# LED_0.net
KiCad netlist of a schematic drawn in Altium Designer
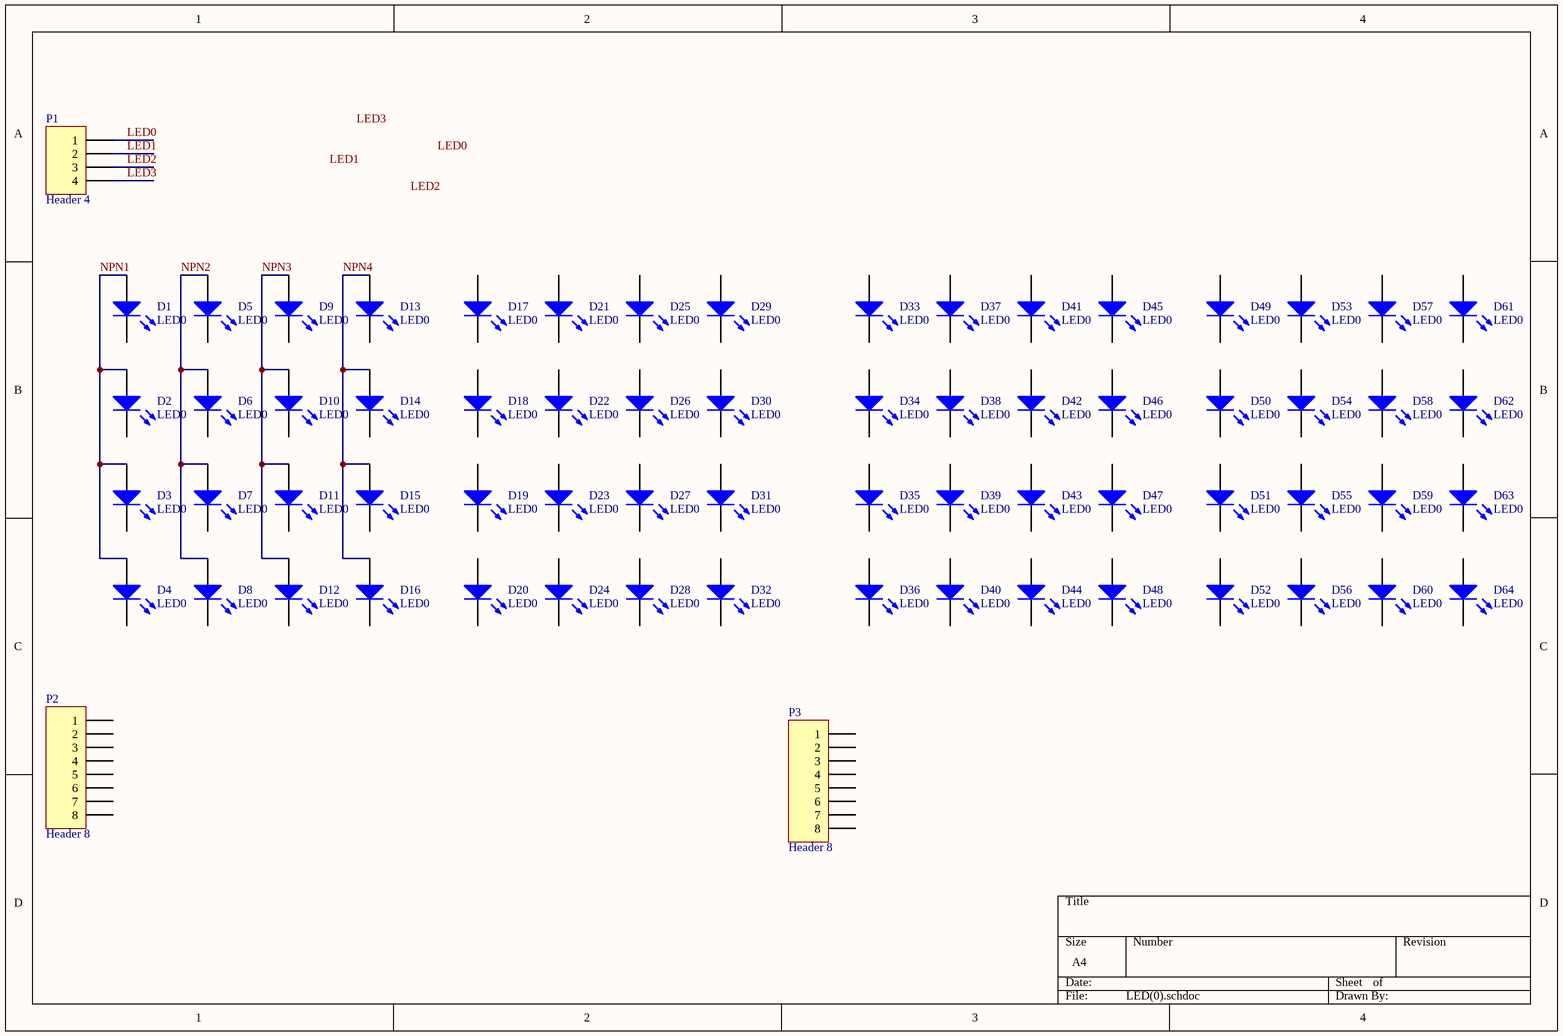
[diagram p0: LED(0).schdoc]

(export (version "E")
  (design (tool "Eeschema 10.0.6"))
  (components
    (comp (ref "D1")
      (value "LED0")
      (footprint "LED-0")
      (description "Typical INFRARED GaAs LED")
      (fields (field (name "PUBLISHER") "Altium Limited"))
      (libsource (lib "Miscellaneous Devices") (part "LED0"))
    )
    (comp (ref "D2")
      (value "LED0")
      (footprint "LED-0")
      (description "Typical INFRARED GaAs LED")
      (fields (field (name "PUBLISHER") "Altium Limited"))
      (libsource (lib "Miscellaneous Devices") (part "LED0"))
    )
    (comp (ref "D3")
      (value "LED0")
      (footprint "LED-0")
      (description "Typical INFRARED GaAs LED")
      (fields (field (name "PUBLISHER") "Altium Limited"))
      (libsource (lib "Miscellaneous Devices") (part "LED0"))
    )
    (comp (ref "D4")
      (value "LED0")
      (footprint "LED-0")
      (description "Typical INFRARED GaAs LED")
      (fields (field (name "PUBLISHER") "Altium Limited"))
      (libsource (lib "Miscellaneous Devices") (part "LED0"))
    )
    (comp (ref "D5")
      (value "LED0")
      (footprint "LED-0")
      (description "Typical INFRARED GaAs LED")
      (fields (field (name "PUBLISHER") "Altium Limited"))
      (libsource (lib "Miscellaneous Devices") (part "LED0"))
    )
    (comp (ref "D6")
      (value "LED0")
      (footprint "LED-0")
      (description "Typical INFRARED GaAs LED")
      (fields (field (name "PUBLISHER") "Altium Limited"))
      (libsource (lib "Miscellaneous Devices") (part "LED0"))
    )
    (comp (ref "D7")
      (value "LED0")
      (footprint "LED-0")
      (description "Typical INFRARED GaAs LED")
      (fields (field (name "PUBLISHER") "Altium Limited"))
      (libsource (lib "Miscellaneous Devices") (part "LED0"))
    )
    (comp (ref "D8")
      (value "LED0")
      (footprint "LED-0")
      (description "Typical INFRARED GaAs LED")
      (fields (field (name "PUBLISHER") "Altium Limited"))
      (libsource (lib "Miscellaneous Devices") (part "LED0"))
    )
    (comp (ref "D9")
      (value "LED0")
      (footprint "LED-0")
      (description "Typical INFRARED GaAs LED")
      (fields (field (name "PUBLISHER") "Altium Limited"))
      (libsource (lib "Miscellaneous Devices") (part "LED0"))
    )
    (comp (ref "D10")
      (value "LED0")
      (footprint "LED-0")
      (description "Typical INFRARED GaAs LED")
      (fields (field (name "PUBLISHER") "Altium Limited"))
      (libsource (lib "Miscellaneous Devices") (part "LED0"))
    )
    (comp (ref "D11")
      (value "LED0")
      (footprint "LED-0")
      (description "Typical INFRARED GaAs LED")
      (fields (field (name "PUBLISHER") "Altium Limited"))
      (libsource (lib "Miscellaneous Devices") (part "LED0"))
    )
    (comp (ref "D12")
      (value "LED0")
      (footprint "LED-0")
      (description "Typical INFRARED GaAs LED")
      (fields (field (name "PUBLISHER") "Altium Limited"))
      (libsource (lib "Miscellaneous Devices") (part "LED0"))
    )
    (comp (ref "D13")
      (value "LED0")
      (footprint "LED-0")
      (description "Typical INFRARED GaAs LED")
      (fields (field (name "PUBLISHER") "Altium Limited"))
      (libsource (lib "Miscellaneous Devices") (part "LED0"))
    )
    (comp (ref "D14")
      (value "LED0")
      (footprint "LED-0")
      (description "Typical INFRARED GaAs LED")
      (fields (field (name "PUBLISHER") "Altium Limited"))
      (libsource (lib "Miscellaneous Devices") (part "LED0"))
    )
    (comp (ref "D15")
      (value "LED0")
      (footprint "LED-0")
      (description "Typical INFRARED GaAs LED")
      (fields (field (name "PUBLISHER") "Altium Limited"))
      (libsource (lib "Miscellaneous Devices") (part "LED0"))
    )
    (comp (ref "D16")
      (value "LED0")
      (footprint "LED-0")
      (description "Typical INFRARED GaAs LED")
      (fields (field (name "PUBLISHER") "Altium Limited"))
      (libsource (lib "Miscellaneous Devices") (part "LED0"))
    )
    (comp (ref "D17")
      (value "LED0")
      (footprint "LED-0")
      (description "Typical INFRARED GaAs LED")
      (fields (field (name "PUBLISHER") "Altium Limited"))
      (libsource (lib "Miscellaneous Devices") (part "LED0"))
    )
    (comp (ref "D18")
      (value "LED0")
      (footprint "LED-0")
      (description "Typical INFRARED GaAs LED")
      (fields (field (name "PUBLISHER") "Altium Limited"))
      (libsource (lib "Miscellaneous Devices") (part "LED0"))
    )
    (comp (ref "D19")
      (value "LED0")
      (footprint "LED-0")
      (description "Typical INFRARED GaAs LED")
      (fields (field (name "PUBLISHER") "Altium Limited"))
      (libsource (lib "Miscellaneous Devices") (part "LED0"))
    )
    (comp (ref "D20")
      (value "LED0")
      (footprint "LED-0")
      (description "Typical INFRARED GaAs LED")
      (fields (field (name "PUBLISHER") "Altium Limited"))
      (libsource (lib "Miscellaneous Devices") (part "LED0"))
    )
    (comp (ref "D21")
      (value "LED0")
      (footprint "LED-0")
      (description "Typical INFRARED GaAs LED")
      (fields (field (name "PUBLISHER") "Altium Limited"))
      (libsource (lib "Miscellaneous Devices") (part "LED0"))
    )
    (comp (ref "D22")
      (value "LED0")
      (footprint "LED-0")
      (description "Typical INFRARED GaAs LED")
      (fields (field (name "PUBLISHER") "Altium Limited"))
      (libsource (lib "Miscellaneous Devices") (part "LED0"))
    )
    (comp (ref "D23")
      (value "LED0")
      (footprint "LED-0")
      (description "Typical INFRARED GaAs LED")
      (fields (field (name "PUBLISHER") "Altium Limited"))
      (libsource (lib "Miscellaneous Devices") (part "LED0"))
    )
    (comp (ref "D24")
      (value "LED0")
      (footprint "LED-0")
      (description "Typical INFRARED GaAs LED")
      (fields (field (name "PUBLISHER") "Altium Limited"))
      (libsource (lib "Miscellaneous Devices") (part "LED0"))
    )
    (comp (ref "D25")
      (value "LED0")
      (footprint "LED-0")
      (description "Typical INFRARED GaAs LED")
      (fields (field (name "PUBLISHER") "Altium Limited"))
      (libsource (lib "Miscellaneous Devices") (part "LED0"))
    )
    (comp (ref "D26")
      (value "LED0")
      (footprint "LED-0")
      (description "Typical INFRARED GaAs LED")
      (fields (field (name "PUBLISHER") "Altium Limited"))
      (libsource (lib "Miscellaneous Devices") (part "LED0"))
    )
    (comp (ref "D27")
      (value "LED0")
      (footprint "LED-0")
      (description "Typical INFRARED GaAs LED")
      (fields (field (name "PUBLISHER") "Altium Limited"))
      (libsource (lib "Miscellaneous Devices") (part "LED0"))
    )
    (comp (ref "D28")
      (value "LED0")
      (footprint "LED-0")
      (description "Typical INFRARED GaAs LED")
      (fields (field (name "PUBLISHER") "Altium Limited"))
      (libsource (lib "Miscellaneous Devices") (part "LED0"))
    )
    (comp (ref "D29")
      (value "LED0")
      (footprint "LED-0")
      (description "Typical INFRARED GaAs LED")
      (fields (field (name "PUBLISHER") "Altium Limited"))
      (libsource (lib "Miscellaneous Devices") (part "LED0"))
    )
    (comp (ref "D30")
      (value "LED0")
      (footprint "LED-0")
      (description "Typical INFRARED GaAs LED")
      (fields (field (name "PUBLISHER") "Altium Limited"))
      (libsource (lib "Miscellaneous Devices") (part "LED0"))
    )
    (comp (ref "D31")
      (value "LED0")
      (footprint "LED-0")
      (description "Typical INFRARED GaAs LED")
      (fields (field (name "PUBLISHER") "Altium Limited"))
      (libsource (lib "Miscellaneous Devices") (part "LED0"))
    )
    (comp (ref "D32")
      (value "LED0")
      (footprint "LED-0")
      (description "Typical INFRARED GaAs LED")
      (fields (field (name "PUBLISHER") "Altium Limited"))
      (libsource (lib "Miscellaneous Devices") (part "LED0"))
    )
    (comp (ref "D33")
      (value "LED0")
      (footprint "LED-0")
      (description "Typical INFRARED GaAs LED")
      (fields (field (name "PUBLISHER") "Altium Limited"))
      (libsource (lib "Miscellaneous Devices") (part "LED0"))
    )
    (comp (ref "D34")
      (value "LED0")
      (footprint "LED-0")
      (description "Typical INFRARED GaAs LED")
      (fields (field (name "PUBLISHER") "Altium Limited"))
      (libsource (lib "Miscellaneous Devices") (part "LED0"))
    )
    (comp (ref "D35")
      (value "LED0")
      (footprint "LED-0")
      (description "Typical INFRARED GaAs LED")
      (fields (field (name "PUBLISHER") "Altium Limited"))
      (libsource (lib "Miscellaneous Devices") (part "LED0"))
    )
    (comp (ref "D36")
      (value "LED0")
      (footprint "LED-0")
      (description "Typical INFRARED GaAs LED")
      (fields (field (name "PUBLISHER") "Altium Limited"))
      (libsource (lib "Miscellaneous Devices") (part "LED0"))
    )
    (comp (ref "D37")
      (value "LED0")
      (footprint "LED-0")
      (description "Typical INFRARED GaAs LED")
      (fields (field (name "PUBLISHER") "Altium Limited"))
      (libsource (lib "Miscellaneous Devices") (part "LED0"))
    )
    (comp (ref "D38")
      (value "LED0")
      (footprint "LED-0")
      (description "Typical INFRARED GaAs LED")
      (fields (field (name "PUBLISHER") "Altium Limited"))
      (libsource (lib "Miscellaneous Devices") (part "LED0"))
    )
    (comp (ref "D39")
      (value "LED0")
      (footprint "LED-0")
      (description "Typical INFRARED GaAs LED")
      (fields (field (name "PUBLISHER") "Altium Limited"))
      (libsource (lib "Miscellaneous Devices") (part "LED0"))
    )
    (comp (ref "D40")
      (value "LED0")
      (footprint "LED-0")
      (description "Typical INFRARED GaAs LED")
      (fields (field (name "PUBLISHER") "Altium Limited"))
      (libsource (lib "Miscellaneous Devices") (part "LED0"))
    )
    (comp (ref "D41")
      (value "LED0")
      (footprint "LED-0")
      (description "Typical INFRARED GaAs LED")
      (fields (field (name "PUBLISHER") "Altium Limited"))
      (libsource (lib "Miscellaneous Devices") (part "LED0"))
    )
    (comp (ref "D42")
      (value "LED0")
      (footprint "LED-0")
      (description "Typical INFRARED GaAs LED")
      (fields (field (name "PUBLISHER") "Altium Limited"))
      (libsource (lib "Miscellaneous Devices") (part "LED0"))
    )
    (comp (ref "D43")
      (value "LED0")
      (footprint "LED-0")
      (description "Typical INFRARED GaAs LED")
      (fields (field (name "PUBLISHER") "Altium Limited"))
      (libsource (lib "Miscellaneous Devices") (part "LED0"))
    )
    (comp (ref "D44")
      (value "LED0")
      (footprint "LED-0")
      (description "Typical INFRARED GaAs LED")
      (fields (field (name "PUBLISHER") "Altium Limited"))
      (libsource (lib "Miscellaneous Devices") (part "LED0"))
    )
    (comp (ref "D45")
      (value "LED0")
      (footprint "LED-0")
      (description "Typical INFRARED GaAs LED")
      (fields (field (name "PUBLISHER") "Altium Limited"))
      (libsource (lib "Miscellaneous Devices") (part "LED0"))
    )
    (comp (ref "D46")
      (value "LED0")
      (footprint "LED-0")
      (description "Typical INFRARED GaAs LED")
      (fields (field (name "PUBLISHER") "Altium Limited"))
      (libsource (lib "Miscellaneous Devices") (part "LED0"))
    )
    (comp (ref "D47")
      (value "LED0")
      (footprint "LED-0")
      (description "Typical INFRARED GaAs LED")
      (fields (field (name "PUBLISHER") "Altium Limited"))
      (libsource (lib "Miscellaneous Devices") (part "LED0"))
    )
    (comp (ref "D48")
      (value "LED0")
      (footprint "LED-0")
      (description "Typical INFRARED GaAs LED")
      (fields (field (name "PUBLISHER") "Altium Limited"))
      (libsource (lib "Miscellaneous Devices") (part "LED0"))
    )
    (comp (ref "D49")
      (value "LED0")
      (footprint "LED-0")
      (description "Typical INFRARED GaAs LED")
      (fields (field (name "PUBLISHER") "Altium Limited"))
      (libsource (lib "Miscellaneous Devices") (part "LED0"))
    )
    (comp (ref "D50")
      (value "LED0")
      (footprint "LED-0")
      (description "Typical INFRARED GaAs LED")
      (fields (field (name "PUBLISHER") "Altium Limited"))
      (libsource (lib "Miscellaneous Devices") (part "LED0"))
    )
    (comp (ref "D51")
      (value "LED0")
      (footprint "LED-0")
      (description "Typical INFRARED GaAs LED")
      (fields (field (name "PUBLISHER") "Altium Limited"))
      (libsource (lib "Miscellaneous Devices") (part "LED0"))
    )
    (comp (ref "D52")
      (value "LED0")
      (footprint "LED-0")
      (description "Typical INFRARED GaAs LED")
      (fields (field (name "PUBLISHER") "Altium Limited"))
      (libsource (lib "Miscellaneous Devices") (part "LED0"))
    )
    (comp (ref "D53")
      (value "LED0")
      (footprint "LED-0")
      (description "Typical INFRARED GaAs LED")
      (fields (field (name "PUBLISHER") "Altium Limited"))
      (libsource (lib "Miscellaneous Devices") (part "LED0"))
    )
    (comp (ref "D54")
      (value "LED0")
      (footprint "LED-0")
      (description "Typical INFRARED GaAs LED")
      (fields (field (name "PUBLISHER") "Altium Limited"))
      (libsource (lib "Miscellaneous Devices") (part "LED0"))
    )
    (comp (ref "D55")
      (value "LED0")
      (footprint "LED-0")
      (description "Typical INFRARED GaAs LED")
      (fields (field (name "PUBLISHER") "Altium Limited"))
      (libsource (lib "Miscellaneous Devices") (part "LED0"))
    )
    (comp (ref "D56")
      (value "LED0")
      (footprint "LED-0")
      (description "Typical INFRARED GaAs LED")
      (fields (field (name "PUBLISHER") "Altium Limited"))
      (libsource (lib "Miscellaneous Devices") (part "LED0"))
    )
    (comp (ref "D57")
      (value "LED0")
      (footprint "LED-0")
      (description "Typical INFRARED GaAs LED")
      (fields (field (name "PUBLISHER") "Altium Limited"))
      (libsource (lib "Miscellaneous Devices") (part "LED0"))
    )
    (comp (ref "D58")
      (value "LED0")
      (footprint "LED-0")
      (description "Typical INFRARED GaAs LED")
      (fields (field (name "PUBLISHER") "Altium Limited"))
      (libsource (lib "Miscellaneous Devices") (part "LED0"))
    )
    (comp (ref "D59")
      (value "LED0")
      (footprint "LED-0")
      (description "Typical INFRARED GaAs LED")
      (fields (field (name "PUBLISHER") "Altium Limited"))
      (libsource (lib "Miscellaneous Devices") (part "LED0"))
    )
    (comp (ref "D60")
      (value "LED0")
      (footprint "LED-0")
      (description "Typical INFRARED GaAs LED")
      (fields (field (name "PUBLISHER") "Altium Limited"))
      (libsource (lib "Miscellaneous Devices") (part "LED0"))
    )
    (comp (ref "D61")
      (value "LED0")
      (footprint "LED-0")
      (description "Typical INFRARED GaAs LED")
      (fields (field (name "PUBLISHER") "Altium Limited"))
      (libsource (lib "Miscellaneous Devices") (part "LED0"))
    )
    (comp (ref "D62")
      (value "LED0")
      (footprint "LED-0")
      (description "Typical INFRARED GaAs LED")
      (fields (field (name "PUBLISHER") "Altium Limited"))
      (libsource (lib "Miscellaneous Devices") (part "LED0"))
    )
    (comp (ref "D63")
      (value "LED0")
      (footprint "LED-0")
      (description "Typical INFRARED GaAs LED")
      (fields (field (name "PUBLISHER") "Altium Limited"))
      (libsource (lib "Miscellaneous Devices") (part "LED0"))
    )
    (comp (ref "D64")
      (value "LED0")
      (footprint "LED-0")
      (description "Typical INFRARED GaAs LED")
      (fields (field (name "PUBLISHER") "Altium Limited"))
      (libsource (lib "Miscellaneous Devices") (part "LED0"))
    )
    (comp (ref "P1")
      (value "Header 4")
      (footprint "HDR1X4")
      (description "Header, 4-Pin")
      (fields (field (name "PUBLISHER") "Altium Limited"))
      (libsource (lib "Miscellaneous Connectors") (part "Header 4"))
    )
    (comp (ref "P2")
      (value "Header 8")
      (footprint "HDR1X8")
      (description "Header, 8-Pin")
      (fields (field (name "PUBLISHER") "Altium Limited"))
      (libsource (lib "Miscellaneous Connectors") (part "Header 8"))
    )
    (comp (ref "P3")
      (value "Header 8")
      (footprint "HDR1X8")
      (description "Header, 8-Pin")
      (fields (field (name "PUBLISHER") "Altium Limited"))
      (libsource (lib "Miscellaneous Connectors") (part "Header 8"))
    )
  )
  (nets
    (net (code "1") (name "/LED0") (class "Default")
      (node (ref "P1") (pin "1") (pinfunction "1_1") (pintype "passive"))
    )
    (net (code "2") (name "/LED1") (class "Default")
      (node (ref "P1") (pin "2") (pinfunction "2_2") (pintype "passive"))
    )
    (net (code "3") (name "/LED2") (class "Default")
      (node (ref "P1") (pin "3") (pinfunction "3_3") (pintype "passive"))
    )
    (net (code "4") (name "/LED3") (class "Default")
      (node (ref "P1") (pin "4") (pinfunction "4_4") (pintype "passive"))
    )
    (net (code "5") (name "/NPN1") (class "Default")
      (node (ref "D1") (pin "1") (pinfunction "A_1") (pintype "passive"))
      (node (ref "D2") (pin "1") (pinfunction "A_1") (pintype "passive"))
      (node (ref "D3") (pin "1") (pinfunction "A_1") (pintype "passive"))
      (node (ref "D4") (pin "1") (pinfunction "A_1") (pintype "passive"))
    )
    (net (code "6") (name "/NPN2") (class "Default")
      (node (ref "D5") (pin "1") (pinfunction "A_1") (pintype "passive"))
      (node (ref "D6") (pin "1") (pinfunction "A_1") (pintype "passive"))
      (node (ref "D7") (pin "1") (pinfunction "A_1") (pintype "passive"))
      (node (ref "D8") (pin "1") (pinfunction "A_1") (pintype "passive"))
    )
    (net (code "7") (name "/NPN3") (class "Default")
      (node (ref "D10") (pin "1") (pinfunction "A_1") (pintype "passive"))
      (node (ref "D11") (pin "1") (pinfunction "A_1") (pintype "passive"))
      (node (ref "D12") (pin "1") (pinfunction "A_1") (pintype "passive"))
      (node (ref "D9") (pin "1") (pinfunction "A_1") (pintype "passive"))
    )
    (net (code "8") (name "/NPN4") (class "Default")
      (node (ref "D13") (pin "1") (pinfunction "A_1") (pintype "passive"))
      (node (ref "D14") (pin "1") (pinfunction "A_1") (pintype "passive"))
      (node (ref "D15") (pin "1") (pinfunction "A_1") (pintype "passive"))
      (node (ref "D16") (pin "1") (pinfunction "A_1") (pintype "passive"))
    )
    (net (code "9") (name "unconnected-(D1-K-Pad2)") (class "Default")
      (node (ref "D1") (pin "2") (pinfunction "K_2") (pintype "passive"))
    )
    (net (code "10") (name "unconnected-(D2-K-Pad2)") (class "Default")
      (node (ref "D2") (pin "2") (pinfunction "K_2") (pintype "passive"))
    )
    (net (code "11") (name "unconnected-(D3-K-Pad2)") (class "Default")
      (node (ref "D3") (pin "2") (pinfunction "K_2") (pintype "passive"))
    )
    (net (code "12") (name "unconnected-(D4-K-Pad2)") (class "Default")
      (node (ref "D4") (pin "2") (pinfunction "K_2") (pintype "passive"))
    )
    (net (code "13") (name "unconnected-(D5-K-Pad2)") (class "Default")
      (node (ref "D5") (pin "2") (pinfunction "K_2") (pintype "passive"))
    )
    (net (code "14") (name "unconnected-(D6-K-Pad2)") (class "Default")
      (node (ref "D6") (pin "2") (pinfunction "K_2") (pintype "passive"))
    )
    (net (code "15") (name "unconnected-(D7-K-Pad2)") (class "Default")
      (node (ref "D7") (pin "2") (pinfunction "K_2") (pintype "passive"))
    )
    (net (code "16") (name "unconnected-(D8-K-Pad2)") (class "Default")
      (node (ref "D8") (pin "2") (pinfunction "K_2") (pintype "passive"))
    )
    (net (code "17") (name "unconnected-(D9-K-Pad2)") (class "Default")
      (node (ref "D9") (pin "2") (pinfunction "K_2") (pintype "passive"))
    )
    (net (code "18") (name "unconnected-(D10-K-Pad2)") (class "Default")
      (node (ref "D10") (pin "2") (pinfunction "K_2") (pintype "passive"))
    )
    (net (code "19") (name "unconnected-(D11-K-Pad2)") (class "Default")
      (node (ref "D11") (pin "2") (pinfunction "K_2") (pintype "passive"))
    )
    (net (code "20") (name "unconnected-(D12-K-Pad2)") (class "Default")
      (node (ref "D12") (pin "2") (pinfunction "K_2") (pintype "passive"))
    )
    (net (code "21") (name "unconnected-(D13-K-Pad2)") (class "Default")
      (node (ref "D13") (pin "2") (pinfunction "K_2") (pintype "passive"))
    )
    (net (code "22") (name "unconnected-(D14-K-Pad2)") (class "Default")
      (node (ref "D14") (pin "2") (pinfunction "K_2") (pintype "passive"))
    )
    (net (code "23") (name "unconnected-(D15-K-Pad2)") (class "Default")
      (node (ref "D15") (pin "2") (pinfunction "K_2") (pintype "passive"))
    )
    (net (code "24") (name "unconnected-(D16-K-Pad2)") (class "Default")
      (node (ref "D16") (pin "2") (pinfunction "K_2") (pintype "passive"))
    )
    (net (code "25") (name "unconnected-(D17-A-Pad1)") (class "Default")
      (node (ref "D17") (pin "1") (pinfunction "A_1") (pintype "passive"))
    )
    (net (code "26") (name "unconnected-(D17-K-Pad2)") (class "Default")
      (node (ref "D17") (pin "2") (pinfunction "K_2") (pintype "passive"))
    )
    (net (code "27") (name "unconnected-(D18-A-Pad1)") (class "Default")
      (node (ref "D18") (pin "1") (pinfunction "A_1") (pintype "passive"))
    )
    (net (code "28") (name "unconnected-(D18-K-Pad2)") (class "Default")
      (node (ref "D18") (pin "2") (pinfunction "K_2") (pintype "passive"))
    )
    (net (code "29") (name "unconnected-(D19-A-Pad1)") (class "Default")
      (node (ref "D19") (pin "1") (pinfunction "A_1") (pintype "passive"))
    )
    (net (code "30") (name "unconnected-(D19-K-Pad2)") (class "Default")
      (node (ref "D19") (pin "2") (pinfunction "K_2") (pintype "passive"))
    )
    (net (code "31") (name "unconnected-(D20-A-Pad1)") (class "Default")
      (node (ref "D20") (pin "1") (pinfunction "A_1") (pintype "passive"))
    )
    (net (code "32") (name "unconnected-(D20-K-Pad2)") (class "Default")
      (node (ref "D20") (pin "2") (pinfunction "K_2") (pintype "passive"))
    )
    (net (code "33") (name "unconnected-(D21-A-Pad1)") (class "Default")
      (node (ref "D21") (pin "1") (pinfunction "A_1") (pintype "passive"))
    )
    (net (code "34") (name "unconnected-(D21-K-Pad2)") (class "Default")
      (node (ref "D21") (pin "2") (pinfunction "K_2") (pintype "passive"))
    )
    (net (code "35") (name "unconnected-(D22-A-Pad1)") (class "Default")
      (node (ref "D22") (pin "1") (pinfunction "A_1") (pintype "passive"))
    )
    (net (code "36") (name "unconnected-(D22-K-Pad2)") (class "Default")
      (node (ref "D22") (pin "2") (pinfunction "K_2") (pintype "passive"))
    )
    (net (code "37") (name "unconnected-(D23-A-Pad1)") (class "Default")
      (node (ref "D23") (pin "1") (pinfunction "A_1") (pintype "passive"))
    )
    (net (code "38") (name "unconnected-(D23-K-Pad2)") (class "Default")
      (node (ref "D23") (pin "2") (pinfunction "K_2") (pintype "passive"))
    )
    (net (code "39") (name "unconnected-(D24-A-Pad1)") (class "Default")
      (node (ref "D24") (pin "1") (pinfunction "A_1") (pintype "passive"))
    )
    (net (code "40") (name "unconnected-(D24-K-Pad2)") (class "Default")
      (node (ref "D24") (pin "2") (pinfunction "K_2") (pintype "passive"))
    )
    (net (code "41") (name "unconnected-(D25-A-Pad1)") (class "Default")
      (node (ref "D25") (pin "1") (pinfunction "A_1") (pintype "passive"))
    )
    (net (code "42") (name "unconnected-(D25-K-Pad2)") (class "Default")
      (node (ref "D25") (pin "2") (pinfunction "K_2") (pintype "passive"))
    )
    (net (code "43") (name "unconnected-(D26-A-Pad1)") (class "Default")
      (node (ref "D26") (pin "1") (pinfunction "A_1") (pintype "passive"))
    )
    (net (code "44") (name "unconnected-(D26-K-Pad2)") (class "Default")
      (node (ref "D26") (pin "2") (pinfunction "K_2") (pintype "passive"))
    )
    (net (code "45") (name "unconnected-(D27-A-Pad1)") (class "Default")
      (node (ref "D27") (pin "1") (pinfunction "A_1") (pintype "passive"))
    )
    (net (code "46") (name "unconnected-(D27-K-Pad2)") (class "Default")
      (node (ref "D27") (pin "2") (pinfunction "K_2") (pintype "passive"))
    )
    (net (code "47") (name "unconnected-(D28-A-Pad1)") (class "Default")
      (node (ref "D28") (pin "1") (pinfunction "A_1") (pintype "passive"))
    )
    (net (code "48") (name "unconnected-(D28-K-Pad2)") (class "Default")
      (node (ref "D28") (pin "2") (pinfunction "K_2") (pintype "passive"))
    )
    (net (code "49") (name "unconnected-(D29-A-Pad1)") (class "Default")
      (node (ref "D29") (pin "1") (pinfunction "A_1") (pintype "passive"))
    )
    (net (code "50") (name "unconnected-(D29-K-Pad2)") (class "Default")
      (node (ref "D29") (pin "2") (pinfunction "K_2") (pintype "passive"))
    )
    (net (code "51") (name "unconnected-(D30-A-Pad1)") (class "Default")
      (node (ref "D30") (pin "1") (pinfunction "A_1") (pintype "passive"))
    )
    (net (code "52") (name "unconnected-(D30-K-Pad2)") (class "Default")
      (node (ref "D30") (pin "2") (pinfunction "K_2") (pintype "passive"))
    )
    (net (code "53") (name "unconnected-(D31-A-Pad1)") (class "Default")
      (node (ref "D31") (pin "1") (pinfunction "A_1") (pintype "passive"))
    )
    (net (code "54") (name "unconnected-(D31-K-Pad2)") (class "Default")
      (node (ref "D31") (pin "2") (pinfunction "K_2") (pintype "passive"))
    )
    (net (code "55") (name "unconnected-(D32-A-Pad1)") (class "Default")
      (node (ref "D32") (pin "1") (pinfunction "A_1") (pintype "passive"))
    )
    (net (code "56") (name "unconnected-(D32-K-Pad2)") (class "Default")
      (node (ref "D32") (pin "2") (pinfunction "K_2") (pintype "passive"))
    )
    (net (code "57") (name "unconnected-(D33-A-Pad1)") (class "Default")
      (node (ref "D33") (pin "1") (pinfunction "A_1") (pintype "passive"))
    )
    (net (code "58") (name "unconnected-(D33-K-Pad2)") (class "Default")
      (node (ref "D33") (pin "2") (pinfunction "K_2") (pintype "passive"))
    )
    (net (code "59") (name "unconnected-(D34-A-Pad1)") (class "Default")
      (node (ref "D34") (pin "1") (pinfunction "A_1") (pintype "passive"))
    )
    (net (code "60") (name "unconnected-(D34-K-Pad2)") (class "Default")
      (node (ref "D34") (pin "2") (pinfunction "K_2") (pintype "passive"))
    )
    (net (code "61") (name "unconnected-(D35-A-Pad1)") (class "Default")
      (node (ref "D35") (pin "1") (pinfunction "A_1") (pintype "passive"))
    )
    (net (code "62") (name "unconnected-(D35-K-Pad2)") (class "Default")
      (node (ref "D35") (pin "2") (pinfunction "K_2") (pintype "passive"))
    )
    (net (code "63") (name "unconnected-(D36-A-Pad1)") (class "Default")
      (node (ref "D36") (pin "1") (pinfunction "A_1") (pintype "passive"))
    )
    (net (code "64") (name "unconnected-(D36-K-Pad2)") (class "Default")
      (node (ref "D36") (pin "2") (pinfunction "K_2") (pintype "passive"))
    )
    (net (code "65") (name "unconnected-(D37-A-Pad1)") (class "Default")
      (node (ref "D37") (pin "1") (pinfunction "A_1") (pintype "passive"))
    )
    (net (code "66") (name "unconnected-(D37-K-Pad2)") (class "Default")
      (node (ref "D37") (pin "2") (pinfunction "K_2") (pintype "passive"))
    )
    (net (code "67") (name "unconnected-(D38-A-Pad1)") (class "Default")
      (node (ref "D38") (pin "1") (pinfunction "A_1") (pintype "passive"))
    )
    (net (code "68") (name "unconnected-(D38-K-Pad2)") (class "Default")
      (node (ref "D38") (pin "2") (pinfunction "K_2") (pintype "passive"))
    )
    (net (code "69") (name "unconnected-(D39-A-Pad1)") (class "Default")
      (node (ref "D39") (pin "1") (pinfunction "A_1") (pintype "passive"))
    )
    (net (code "70") (name "unconnected-(D39-K-Pad2)") (class "Default")
      (node (ref "D39") (pin "2") (pinfunction "K_2") (pintype "passive"))
    )
    (net (code "71") (name "unconnected-(D40-A-Pad1)") (class "Default")
      (node (ref "D40") (pin "1") (pinfunction "A_1") (pintype "passive"))
    )
    (net (code "72") (name "unconnected-(D40-K-Pad2)") (class "Default")
      (node (ref "D40") (pin "2") (pinfunction "K_2") (pintype "passive"))
    )
    (net (code "73") (name "unconnected-(D41-A-Pad1)") (class "Default")
      (node (ref "D41") (pin "1") (pinfunction "A_1") (pintype "passive"))
    )
    (net (code "74") (name "unconnected-(D41-K-Pad2)") (class "Default")
      (node (ref "D41") (pin "2") (pinfunction "K_2") (pintype "passive"))
    )
    (net (code "75") (name "unconnected-(D42-A-Pad1)") (class "Default")
      (node (ref "D42") (pin "1") (pinfunction "A_1") (pintype "passive"))
    )
    (net (code "76") (name "unconnected-(D42-K-Pad2)") (class "Default")
      (node (ref "D42") (pin "2") (pinfunction "K_2") (pintype "passive"))
    )
    (net (code "77") (name "unconnected-(D43-A-Pad1)") (class "Default")
      (node (ref "D43") (pin "1") (pinfunction "A_1") (pintype "passive"))
    )
    (net (code "78") (name "unconnected-(D43-K-Pad2)") (class "Default")
      (node (ref "D43") (pin "2") (pinfunction "K_2") (pintype "passive"))
    )
    (net (code "79") (name "unconnected-(D44-A-Pad1)") (class "Default")
      (node (ref "D44") (pin "1") (pinfunction "A_1") (pintype "passive"))
    )
    (net (code "80") (name "unconnected-(D44-K-Pad2)") (class "Default")
      (node (ref "D44") (pin "2") (pinfunction "K_2") (pintype "passive"))
    )
    (net (code "81") (name "unconnected-(D45-A-Pad1)") (class "Default")
      (node (ref "D45") (pin "1") (pinfunction "A_1") (pintype "passive"))
    )
    (net (code "82") (name "unconnected-(D45-K-Pad2)") (class "Default")
      (node (ref "D45") (pin "2") (pinfunction "K_2") (pintype "passive"))
    )
    (net (code "83") (name "unconnected-(D46-A-Pad1)") (class "Default")
      (node (ref "D46") (pin "1") (pinfunction "A_1") (pintype "passive"))
    )
    (net (code "84") (name "unconnected-(D46-K-Pad2)") (class "Default")
      (node (ref "D46") (pin "2") (pinfunction "K_2") (pintype "passive"))
    )
    (net (code "85") (name "unconnected-(D47-A-Pad1)") (class "Default")
      (node (ref "D47") (pin "1") (pinfunction "A_1") (pintype "passive"))
    )
    (net (code "86") (name "unconnected-(D47-K-Pad2)") (class "Default")
      (node (ref "D47") (pin "2") (pinfunction "K_2") (pintype "passive"))
    )
    (net (code "87") (name "unconnected-(D48-A-Pad1)") (class "Default")
      (node (ref "D48") (pin "1") (pinfunction "A_1") (pintype "passive"))
    )
    (net (code "88") (name "unconnected-(D48-K-Pad2)") (class "Default")
      (node (ref "D48") (pin "2") (pinfunction "K_2") (pintype "passive"))
    )
    (net (code "89") (name "unconnected-(D49-A-Pad1)") (class "Default")
      (node (ref "D49") (pin "1") (pinfunction "A_1") (pintype "passive"))
    )
    (net (code "90") (name "unconnected-(D49-K-Pad2)") (class "Default")
      (node (ref "D49") (pin "2") (pinfunction "K_2") (pintype "passive"))
    )
    (net (code "91") (name "unconnected-(D50-A-Pad1)") (class "Default")
      (node (ref "D50") (pin "1") (pinfunction "A_1") (pintype "passive"))
    )
    (net (code "92") (name "unconnected-(D50-K-Pad2)") (class "Default")
      (node (ref "D50") (pin "2") (pinfunction "K_2") (pintype "passive"))
    )
    (net (code "93") (name "unconnected-(D51-A-Pad1)") (class "Default")
      (node (ref "D51") (pin "1") (pinfunction "A_1") (pintype "passive"))
    )
    (net (code "94") (name "unconnected-(D51-K-Pad2)") (class "Default")
      (node (ref "D51") (pin "2") (pinfunction "K_2") (pintype "passive"))
    )
    (net (code "95") (name "unconnected-(D52-A-Pad1)") (class "Default")
      (node (ref "D52") (pin "1") (pinfunction "A_1") (pintype "passive"))
    )
    (net (code "96") (name "unconnected-(D52-K-Pad2)") (class "Default")
      (node (ref "D52") (pin "2") (pinfunction "K_2") (pintype "passive"))
    )
    (net (code "97") (name "unconnected-(D53-A-Pad1)") (class "Default")
      (node (ref "D53") (pin "1") (pinfunction "A_1") (pintype "passive"))
    )
    (net (code "98") (name "unconnected-(D53-K-Pad2)") (class "Default")
      (node (ref "D53") (pin "2") (pinfunction "K_2") (pintype "passive"))
    )
    (net (code "99") (name "unconnected-(D54-A-Pad1)") (class "Default")
      (node (ref "D54") (pin "1") (pinfunction "A_1") (pintype "passive"))
    )
    (net (code "100") (name "unconnected-(D54-K-Pad2)") (class "Default")
      (node (ref "D54") (pin "2") (pinfunction "K_2") (pintype "passive"))
    )
    (net (code "101") (name "unconnected-(D55-A-Pad1)") (class "Default")
      (node (ref "D55") (pin "1") (pinfunction "A_1") (pintype "passive"))
    )
    (net (code "102") (name "unconnected-(D55-K-Pad2)") (class "Default")
      (node (ref "D55") (pin "2") (pinfunction "K_2") (pintype "passive"))
    )
    (net (code "103") (name "unconnected-(D56-A-Pad1)") (class "Default")
      (node (ref "D56") (pin "1") (pinfunction "A_1") (pintype "passive"))
    )
    (net (code "104") (name "unconnected-(D56-K-Pad2)") (class "Default")
      (node (ref "D56") (pin "2") (pinfunction "K_2") (pintype "passive"))
    )
    (net (code "105") (name "unconnected-(D57-A-Pad1)") (class "Default")
      (node (ref "D57") (pin "1") (pinfunction "A_1") (pintype "passive"))
    )
    (net (code "106") (name "unconnected-(D57-K-Pad2)") (class "Default")
      (node (ref "D57") (pin "2") (pinfunction "K_2") (pintype "passive"))
    )
    (net (code "107") (name "unconnected-(D58-A-Pad1)") (class "Default")
      (node (ref "D58") (pin "1") (pinfunction "A_1") (pintype "passive"))
    )
    (net (code "108") (name "unconnected-(D58-K-Pad2)") (class "Default")
      (node (ref "D58") (pin "2") (pinfunction "K_2") (pintype "passive"))
    )
    (net (code "109") (name "unconnected-(D59-A-Pad1)") (class "Default")
      (node (ref "D59") (pin "1") (pinfunction "A_1") (pintype "passive"))
    )
    (net (code "110") (name "unconnected-(D59-K-Pad2)") (class "Default")
      (node (ref "D59") (pin "2") (pinfunction "K_2") (pintype "passive"))
    )
    (net (code "111") (name "unconnected-(D60-A-Pad1)") (class "Default")
      (node (ref "D60") (pin "1") (pinfunction "A_1") (pintype "passive"))
    )
    (net (code "112") (name "unconnected-(D60-K-Pad2)") (class "Default")
      (node (ref "D60") (pin "2") (pinfunction "K_2") (pintype "passive"))
    )
    (net (code "113") (name "unconnected-(D61-A-Pad1)") (class "Default")
      (node (ref "D61") (pin "1") (pinfunction "A_1") (pintype "passive"))
    )
    (net (code "114") (name "unconnected-(D61-K-Pad2)") (class "Default")
      (node (ref "D61") (pin "2") (pinfunction "K_2") (pintype "passive"))
    )
    (net (code "115") (name "unconnected-(D62-A-Pad1)") (class "Default")
      (node (ref "D62") (pin "1") (pinfunction "A_1") (pintype "passive"))
    )
    (net (code "116") (name "unconnected-(D62-K-Pad2)") (class "Default")
      (node (ref "D62") (pin "2") (pinfunction "K_2") (pintype "passive"))
    )
    (net (code "117") (name "unconnected-(D63-A-Pad1)") (class "Default")
      (node (ref "D63") (pin "1") (pinfunction "A_1") (pintype "passive"))
    )
    (net (code "118") (name "unconnected-(D63-K-Pad2)") (class "Default")
      (node (ref "D63") (pin "2") (pinfunction "K_2") (pintype "passive"))
    )
    (net (code "119") (name "unconnected-(D64-A-Pad1)") (class "Default")
      (node (ref "D64") (pin "1") (pinfunction "A_1") (pintype "passive"))
    )
    (net (code "120") (name "unconnected-(D64-K-Pad2)") (class "Default")
      (node (ref "D64") (pin "2") (pinfunction "K_2") (pintype "passive"))
    )
    (net (code "121") (name "unconnected-(P2-Pad1)") (class "Default")
      (node (ref "P2") (pin "1") (pinfunction "1_1") (pintype "passive"))
    )
    (net (code "122") (name "unconnected-(P2-Pad2)") (class "Default")
      (node (ref "P2") (pin "2") (pinfunction "2_2") (pintype "passive"))
    )
    (net (code "123") (name "unconnected-(P2-Pad3)") (class "Default")
      (node (ref "P2") (pin "3") (pinfunction "3_3") (pintype "passive"))
    )
    (net (code "124") (name "unconnected-(P2-Pad4)") (class "Default")
      (node (ref "P2") (pin "4") (pinfunction "4_4") (pintype "passive"))
    )
    (net (code "125") (name "unconnected-(P2-Pad5)") (class "Default")
      (node (ref "P2") (pin "5") (pinfunction "5_5") (pintype "passive"))
    )
    (net (code "126") (name "unconnected-(P2-Pad6)") (class "Default")
      (node (ref "P2") (pin "6") (pinfunction "6_6") (pintype "passive"))
    )
    (net (code "127") (name "unconnected-(P2-Pad7)") (class "Default")
      (node (ref "P2") (pin "7") (pinfunction "7_7") (pintype "passive"))
    )
    (net (code "128") (name "unconnected-(P2-Pad8)") (class "Default")
      (node (ref "P2") (pin "8") (pinfunction "8_8") (pintype "passive"))
    )
    (net (code "129") (name "unconnected-(P3-Pad1)") (class "Default")
      (node (ref "P3") (pin "1") (pinfunction "1_1") (pintype "passive"))
    )
    (net (code "130") (name "unconnected-(P3-Pad2)") (class "Default")
      (node (ref "P3") (pin "2") (pinfunction "2_2") (pintype "passive"))
    )
    (net (code "131") (name "unconnected-(P3-Pad3)") (class "Default")
      (node (ref "P3") (pin "3") (pinfunction "3_3") (pintype "passive"))
    )
    (net (code "132") (name "unconnected-(P3-Pad4)") (class "Default")
      (node (ref "P3") (pin "4") (pinfunction "4_4") (pintype "passive"))
    )
    (net (code "133") (name "unconnected-(P3-Pad5)") (class "Default")
      (node (ref "P3") (pin "5") (pinfunction "5_5") (pintype "passive"))
    )
    (net (code "134") (name "unconnected-(P3-Pad6)") (class "Default")
      (node (ref "P3") (pin "6") (pinfunction "6_6") (pintype "passive"))
    )
    (net (code "135") (name "unconnected-(P3-Pad7)") (class "Default")
      (node (ref "P3") (pin "7") (pinfunction "7_7") (pintype "passive"))
    )
    (net (code "136") (name "unconnected-(P3-Pad8)") (class "Default")
      (node (ref "P3") (pin "8") (pinfunction "8_8") (pintype "passive"))
    )
  )
)
